# 02_Connectors.net
KiCad netlist of a schematic drawn in Altium Designer
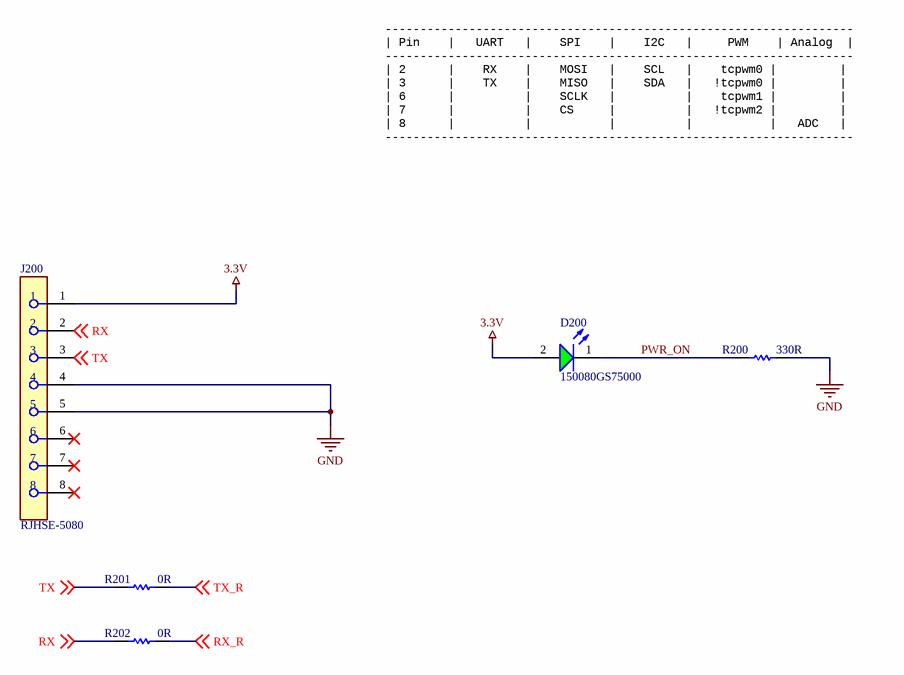
[diagram p0: 02_Connectors.SchDoc]

(export (version "E")
  (design (tool "Eeschema 10.0.6"))
  (components
    (comp (ref "D200")
      (value "150080GS75000")
      (footprint "WL-SMCW_0805_150080xx75000")
      (fields (field (name "MANUFACTURER") "Wurth Electronics"))
      (libsource (lib "Altium Content Vault") (part "LED_Green_2A-1K"))
    )
    (comp (ref "J200")
      (value "RJHSE-5080")
      (footprint "FP-RJHSE-5080-MFG")
      (description "CONN MOD JACK 8P8C R/A UNSHLD")
      (fields
        (field (name "OCTOPART") "https://octopart.com/rjhse-5080-amphenol-45060")
        (field (name "MANUFACTURER") "Amphenol")
      )
      (libsource (lib "Altium Content Vault") (part "b0a0b555dd3abf3683e7c330df25cc4"))
    )
    (comp (ref "R200")
      (value "330R")
      (footprint "RESC2013X60X40LL20T25")
      (fields
        (field (name "MANUFACTURER") "Panasonic")
        (field (name "PART NUMBER") "ERA6AEB331V")
        (field (name "MANUFACTURER PART NUMBER") "ERA-6AEB331V")
      )
      (libsource (lib "Altium Content Vault") (part "RES"))
    )
    (comp (ref "R201")
      (value "0R")
      (footprint "RESC2013X70X40NL20T20")
      (description "Chip Resistor, 0 Ohm, +/- 1%, 0.125 W, -55 to 155 degC, 0805 (2012 Metric), RoHS, Tape and Reel")
      (fields (field (name "PARTNUMBER") "ERJ-6GEY0R00V") (field (name "TOLERANCE") "5%"))
      (libsource (lib "Altium Content Vault") (part "RES-2"))
    )
    (comp (ref "R202")
      (value "0R")
      (footprint "RESC2013X70X40NL20T20")
      (description "Chip Resistor, 0 Ohm, +/- 1%, 0.125 W, -55 to 155 degC, 0805 (2012 Metric), RoHS, Tape and Reel")
      (fields (field (name "PARTNUMBER") "ERJ-6GEY0R00V") (field (name "TOLERANCE") "5%"))
      (libsource (lib "Altium Content Vault") (part "RES-2"))
    )
  )
  (nets
    (net (code "1") (name "/PWR_ON") (class "Default")
      (node (ref "D200") (pin "1") (pinfunction "K_1") (pintype "passive"))
      (node (ref "R200") (pin "1") (pinfunction "1_1") (pintype "passive"))
    )
    (net (code "2") (name "3.3V") (class "Default")
      (node (ref "D200") (pin "2") (pinfunction "A_2") (pintype "passive"))
      (node (ref "J200") (pin "1") (pinfunction "1_1") (pintype "passive"))
    )
    (net (code "3") (name "GND") (class "Default")
      (node (ref "J200") (pin "4") (pinfunction "4_4") (pintype "passive"))
      (node (ref "J200") (pin "5") (pinfunction "5_5") (pintype "passive"))
      (node (ref "R200") (pin "2") (pinfunction "2_2") (pintype "passive"))
    )
    (net (code "4") (name "RX") (class "Default")
      (node (ref "J200") (pin "2") (pinfunction "2_2") (pintype "passive"))
      (node (ref "R202") (pin "1") (pinfunction "1_1") (pintype "passive"))
    )
    (net (code "5") (name "RX_R") (class "Default")
      (node (ref "R202") (pin "2") (pinfunction "2_2") (pintype "passive"))
    )
    (net (code "6") (name "TX") (class "Default")
      (node (ref "J200") (pin "3") (pinfunction "3_3") (pintype "passive"))
      (node (ref "R201") (pin "1") (pinfunction "1_1") (pintype "passive"))
    )
    (net (code "7") (name "TX_R") (class "Default")
      (node (ref "R201") (pin "2") (pinfunction "2_2") (pintype "passive"))
    )
    (net (code "8") (name "unconnected-(J200-Pad6)") (class "Default")
      (node (ref "J200") (pin "6") (pinfunction "6_6") (pintype "passive+no_connect"))
    )
    (net (code "9") (name "unconnected-(J200-Pad7)") (class "Default")
      (node (ref "J200") (pin "7") (pinfunction "7_7") (pintype "passive+no_connect"))
    )
    (net (code "10") (name "unconnected-(J200-Pad8)") (class "Default")
      (node (ref "J200") (pin "8") (pinfunction "8_8") (pintype "passive+no_connect"))
    )
  )
)
